# Power.net
KiCad netlist of a schematic drawn in Altium Designer
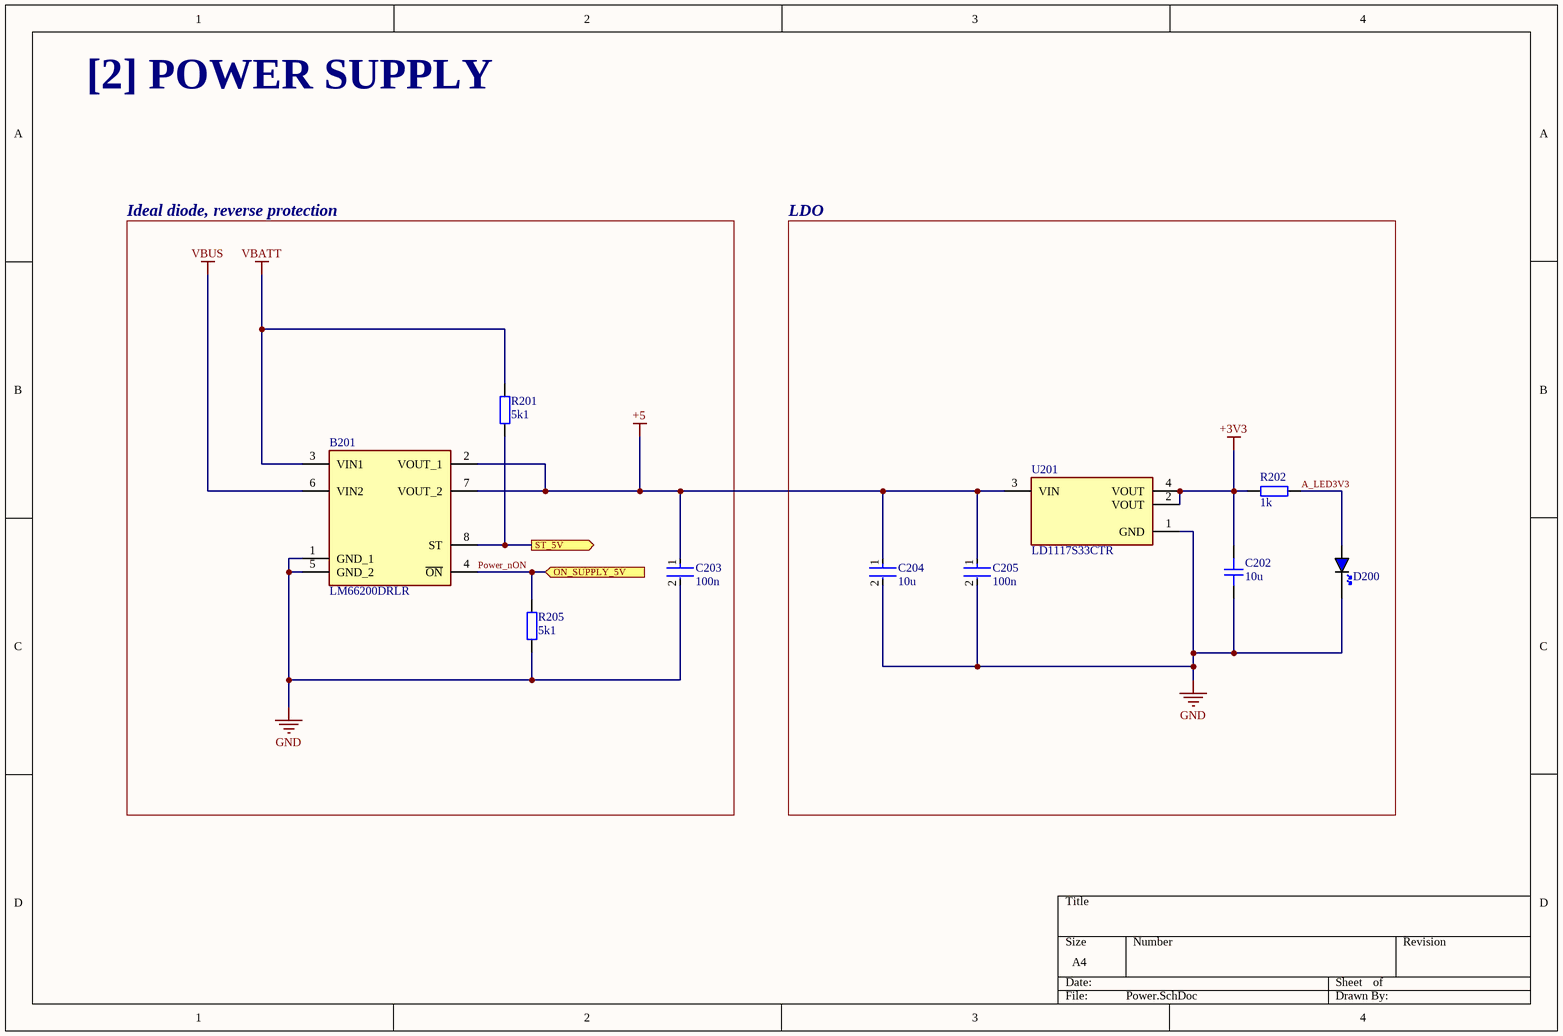
[diagram p0: Power.SchDoc]

(export (version "E")
  (design (tool "Eeschema 10.0.6"))
  (components
    (comp (ref "B201")
      (value "LM66200DRLR")
      (footprint "SOTFL50P160X60-8N")
      (description "1.6-V to 5.5-V, 40-m, 2.5-A, low-IQ, dual ideal diode")
      (fields (field (name "MOUSER PART NUMBER") "595-LM66200DRLR"))
      (libsource (lib "SCHEM_FC_NAVC_LIB") (part "LM66200DRLR"))
    )
    (comp (ref "C202")
      (value "10u")
      (footprint "CAP_0603")
      (description "Capacitor SMD 0603")
      (libsource (lib "Schematic-Lib-PhilsLab") (part "CAP_0603"))
    )
    (comp (ref "C203")
      (value "100n")
      (footprint "FP-CL779-IPC_C")
      (description "Cap Ceramic 100nF 50V X7R ±10% SMD 0402 +125°C Paper T/R CL05B104KB54PNC")
      (libsource (lib "Altium Content Vault") (part "b4654b650e69147ec39a6b967a45e02"))
    )
    (comp (ref "C204")
      (value "10u")
      (footprint "FP-CL10-IPC_C")
      (description "Cap Ceramic 10uF 25V X5R ±20% Pad SMD 0603 +85°C T/R CL10A106MA8NRNC")
      (fields (field (name "TOLERANCE") "20%"))
      (libsource (lib "Altium Content Vault") (part "b4654b650e69147ec39a6b967a45e02"))
    )
    (comp (ref "C205")
      (value "100n")
      (footprint "FP-CL779-IPC_C")
      (description "Cap Ceramic 100nF 50V X7R ±10% SMD 0402 +125°C Paper T/R CL05B104KB54PNC")
      (libsource (lib "Altium Content Vault") (part "b4654b650e69147ec39a6b967a45e02"))
    )
    (comp (ref "D200")
      (value "BLUE")
      (footprint "LED_0603_BLUE")
      (description "LED 0603 BLUE SMD")
      (libsource (lib "Schematic-Lib-PhilsLab") (part "LED_0603_BLUE"))
    )
    (comp (ref "R201")
      (value "5k1")
      (footprint "RES_0402")
      (description "Resistor SMD 0402")
      (libsource (lib "Schematic-Lib-PhilsLab") (part "RES_0402"))
    )
    (comp (ref "R202")
      (value "1k")
      (footprint "RES_0603")
      (description "Resistor SMD 0603")
      (libsource (lib "Schematic-Lib-PhilsLab") (part "RES_0603"))
    )
    (comp (ref "R205")
      (value "5k1")
      (footprint "RES_0402")
      (description "Resistor SMD 0402")
      (libsource (lib "Schematic-Lib-PhilsLab") (part "RES_0402"))
    )
    (comp (ref "U201")
      (value "LD1117S33CTR")
      (footprint "FP-SOT-223-0046067_14-MFG")
      (description "IC REG LINEAR 3.3V 800MA SOT223")
      (libsource (lib "Altium Content Vault") (part "7818869c5c16ceab15634627166a29d"))
    )
  )
  (nets
    (net (code "1") (name "+3V3") (class "Default")
      (node (ref "C202") (pin "2") (pinfunction "2_2") (pintype "passive"))
      (node (ref "R202") (pin "2") (pinfunction "2_2") (pintype "passive"))
      (node (ref "U201") (pin "2") (pinfunction "VOUT_2") (pintype "power_in"))
      (node (ref "U201") (pin "4") (pinfunction "VOUT_4") (pintype "power_in"))
    )
    (net (code "2") (name "+5") (class "Default")
      (node (ref "B201") (pin "2") (pinfunction "VOUT_1_2") (pintype "passive"))
      (node (ref "B201") (pin "7") (pinfunction "VOUT_2_7") (pintype "passive"))
      (node (ref "C203") (pin "1") (pinfunction "1_1") (pintype "passive"))
      (node (ref "C204") (pin "1") (pinfunction "1_1") (pintype "passive"))
      (node (ref "C205") (pin "1") (pinfunction "1_1") (pintype "passive"))
      (node (ref "U201") (pin "3") (pinfunction "VIN_3") (pintype "power_in"))
    )
    (net (code "3") (name "/A_LED3V3") (class "Default")
      (node (ref "D200") (pin "A") (pinfunction "A_A") (pintype "passive"))
      (node (ref "R202") (pin "1") (pinfunction "1_1") (pintype "passive"))
    )
    (net (code "4") (name "/Power_nON") (class "Default")
      (node (ref "B201") (pin "4") (pinfunction "~{ON}_4") (pintype "passive"))
      (node (ref "R205") (pin "1") (pinfunction "1_1") (pintype "passive"))
    )
    (net (code "5") (name "/ST_5V") (class "Default")
      (node (ref "B201") (pin "8") (pinfunction "ST_8") (pintype "passive"))
      (node (ref "R201") (pin "2") (pinfunction "2_2") (pintype "passive"))
    )
    (net (code "6") (name "GND") (class "Default")
      (node (ref "B201") (pin "1") (pinfunction "GND_1_1") (pintype "passive"))
      (node (ref "B201") (pin "5") (pinfunction "GND_2_5") (pintype "passive"))
      (node (ref "C202") (pin "1") (pinfunction "1_1") (pintype "passive"))
      (node (ref "C203") (pin "2") (pinfunction "2_2") (pintype "passive"))
      (node (ref "C204") (pin "2") (pinfunction "2_2") (pintype "passive"))
      (node (ref "C205") (pin "2") (pinfunction "2_2") (pintype "passive"))
      (node (ref "D200") (pin "K") (pinfunction "K_K") (pintype "passive"))
      (node (ref "R205") (pin "2") (pinfunction "2_2") (pintype "passive"))
      (node (ref "U201") (pin "1") (pinfunction "GND_1") (pintype "power_in"))
    )
    (net (code "7") (name "VBATT") (class "Default")
      (node (ref "B201") (pin "3") (pinfunction "VIN1_3") (pintype "passive"))
      (node (ref "R201") (pin "1") (pinfunction "1_1") (pintype "passive"))
    )
    (net (code "8") (name "VBUS") (class "Default")
      (node (ref "B201") (pin "6") (pinfunction "VIN2_6") (pintype "passive"))
    )
  )
)
